# SCH_Output_register_2021-10-31.net
KiCad netlist of a schematic drawn in EasyEDA
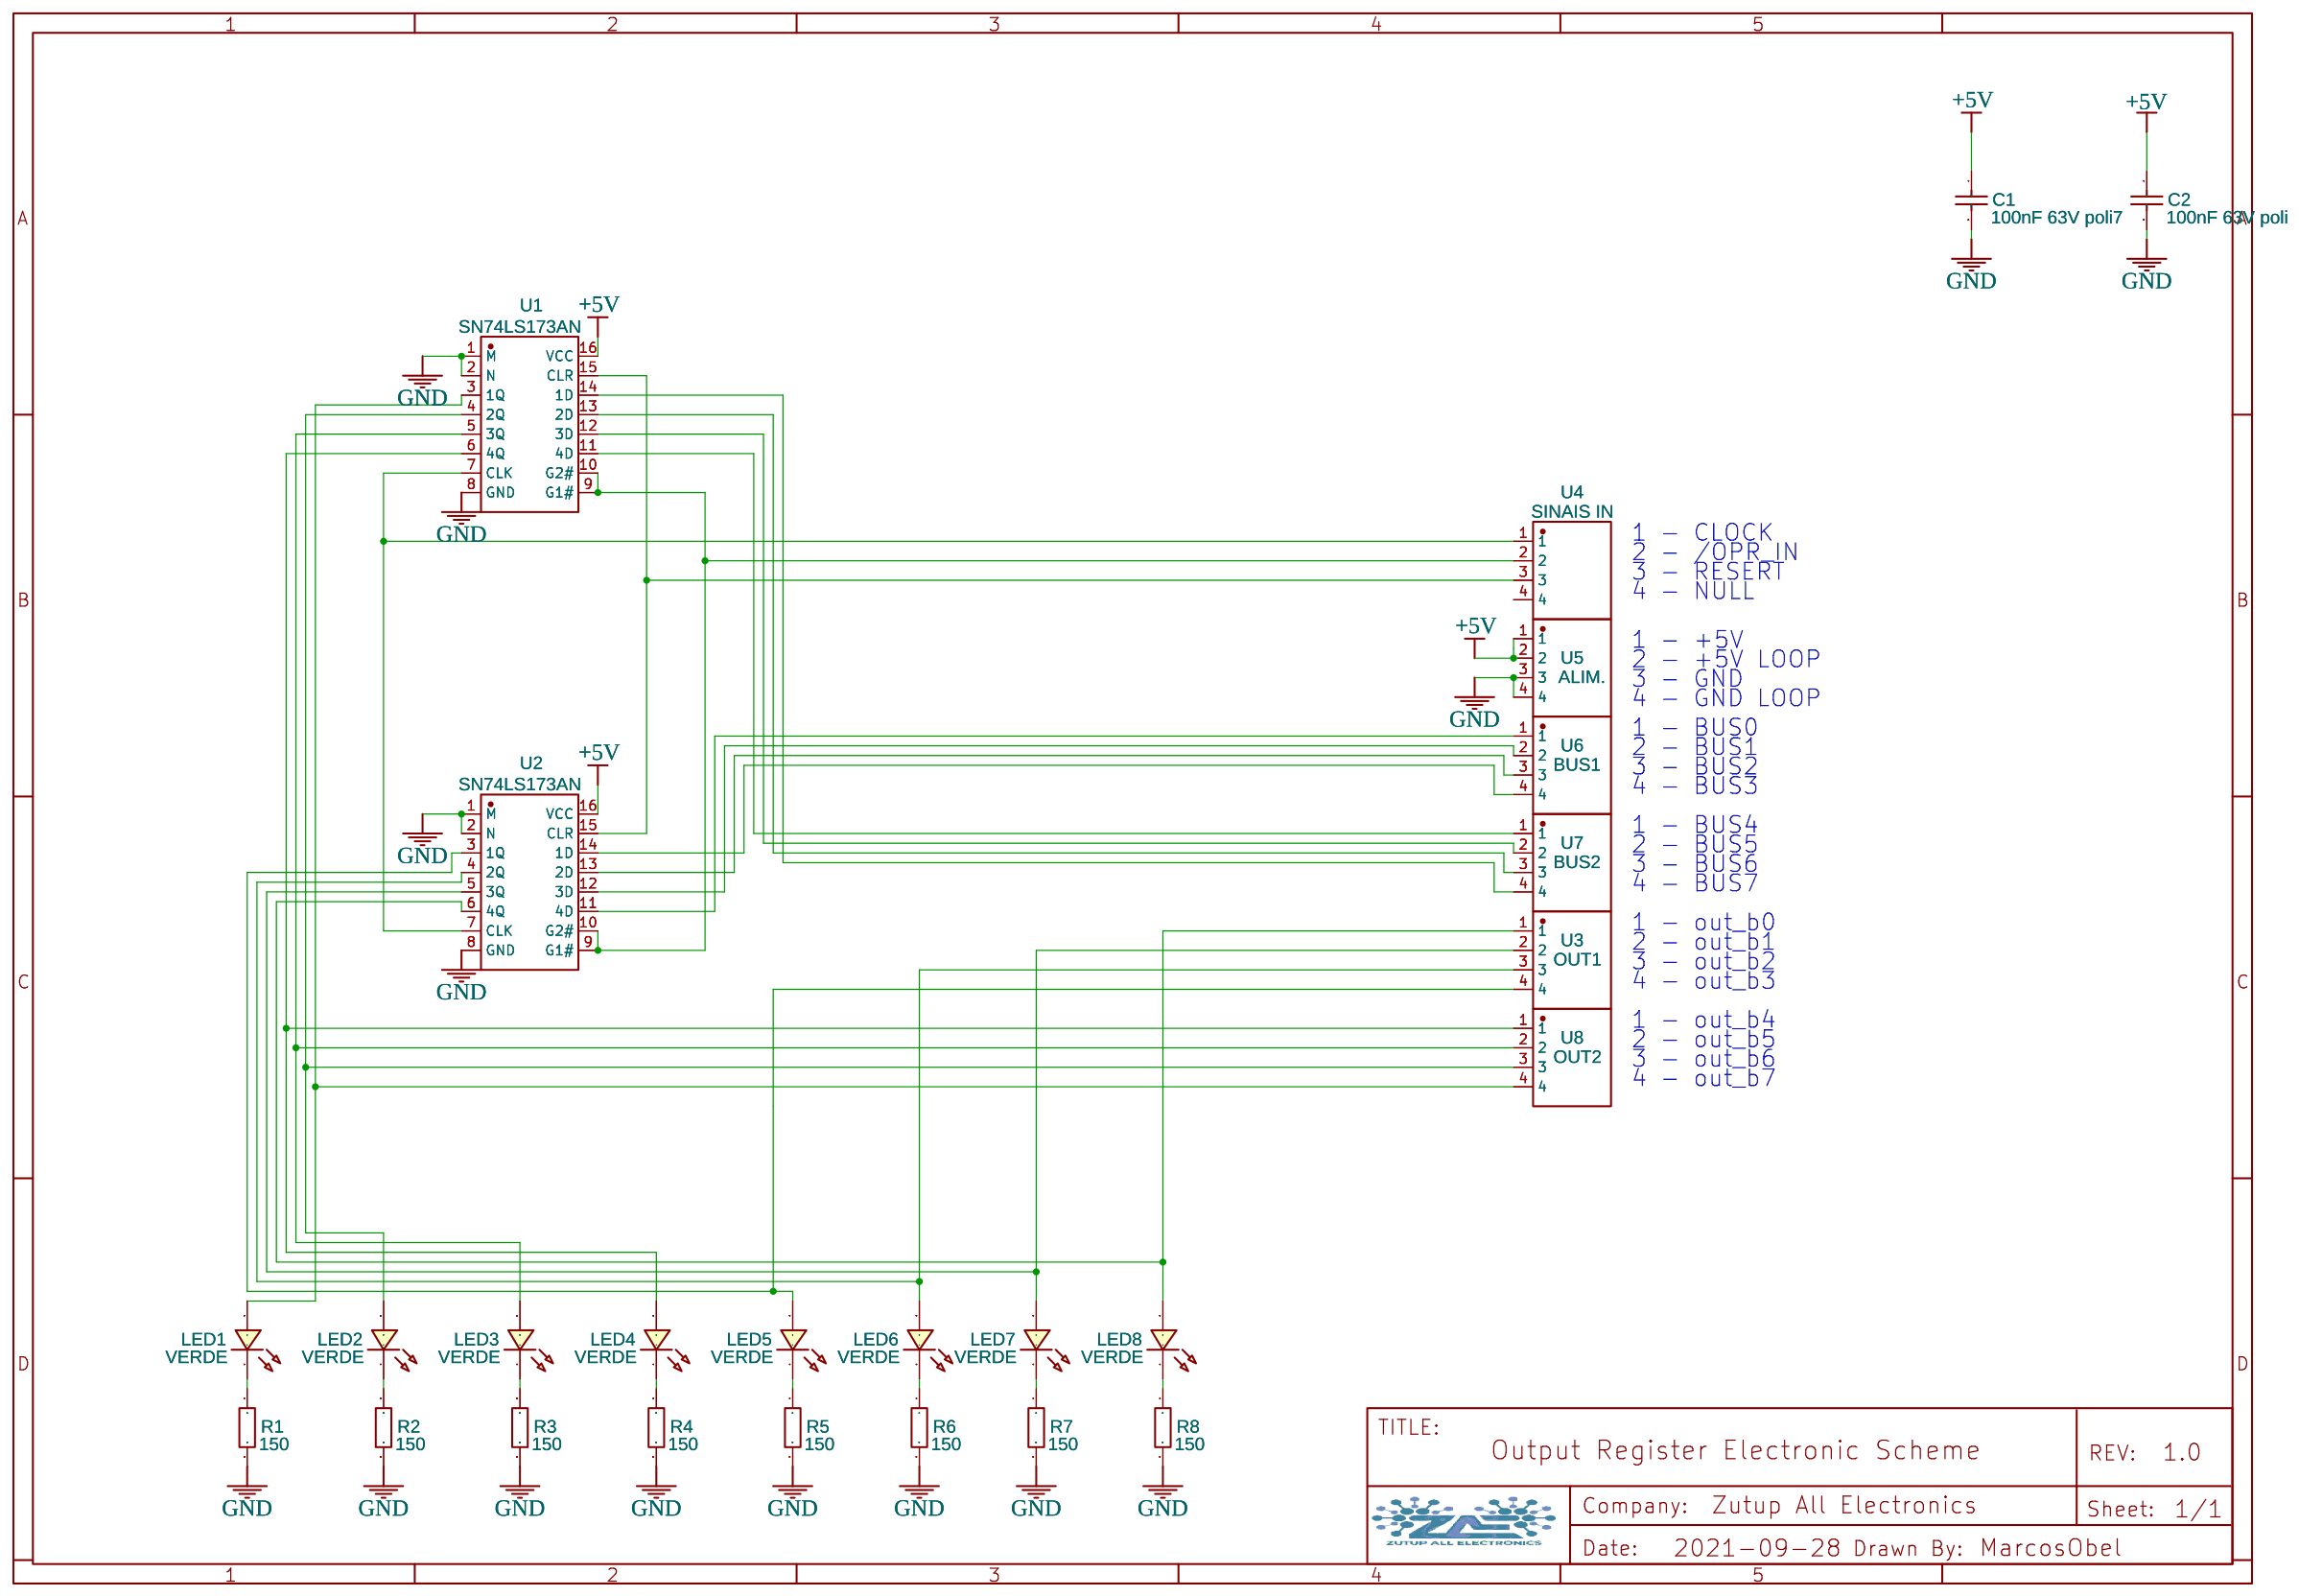
[diagram p0: schematic sheet]

(export (version "E")
  (design (tool "Eeschema 10.0.6"))
  (components
    (comp (ref "C1")
      (value "100nF 63V poli7")
      (fields
        (field (name "BOM_Manufacturer Part") "SR305C105KAR")
        (field (name "BOM_Supplier Part") "C444741")
      )
      (libsource (lib "") (part "SR305C105KAR"))
    )
    (comp (ref "C2")
      (value "100nF 63V poli")
      (fields
        (field (name "BOM_Manufacturer Part") "SR305C105KAR")
        (field (name "BOM_Supplier Part") "C444741")
      )
      (libsource (lib "") (part "SR305C105KAR"))
    )
    (comp (ref "LED1")
      (value "VERDE")
      (fields (field (name "BOM_Manufacturer Part") "264-7GD") (field (name "BOM_Supplier Part") "C605465"))
      (libsource (lib "") (part "264-7GD"))
    )
    (comp (ref "LED2")
      (value "VERDE")
      (fields (field (name "BOM_Manufacturer Part") "264-7GD") (field (name "BOM_Supplier Part") "C605465"))
      (libsource (lib "") (part "264-7GD"))
    )
    (comp (ref "LED3")
      (value "VERDE")
      (fields (field (name "BOM_Manufacturer Part") "264-7GD") (field (name "BOM_Supplier Part") "C605465"))
      (libsource (lib "") (part "264-7GD"))
    )
    (comp (ref "LED4")
      (value "VERDE")
      (fields (field (name "BOM_Manufacturer Part") "264-7GD") (field (name "BOM_Supplier Part") "C605465"))
      (libsource (lib "") (part "264-7GD"))
    )
    (comp (ref "LED5")
      (value "VERDE")
      (fields (field (name "BOM_Manufacturer Part") "264-7GD") (field (name "BOM_Supplier Part") "C605465"))
      (libsource (lib "") (part "264-7GD"))
    )
    (comp (ref "LED6")
      (value "VERDE")
      (fields (field (name "BOM_Manufacturer Part") "264-7GD") (field (name "BOM_Supplier Part") "C605465"))
      (libsource (lib "") (part "264-7GD"))
    )
    (comp (ref "LED7")
      (value "VERDE")
      (fields (field (name "BOM_Manufacturer Part") "264-7GD") (field (name "BOM_Supplier Part") "C605465"))
      (libsource (lib "") (part "264-7GD"))
    )
    (comp (ref "LED8")
      (value "VERDE")
      (fields (field (name "BOM_Manufacturer Part") "264-7GD") (field (name "BOM_Supplier Part") "C605465"))
      (libsource (lib "") (part "264-7GD"))
    )
    (comp (ref "R1")
      (value "150")
      (fields
        (field (name "BOM_Manufacturer Part") "CFR02SJ0823A10")
        (field (name "BOM_Supplier Part") "C69876")
      )
      (libsource (lib "") (part "CFR02SJ0823A10"))
    )
    (comp (ref "R2")
      (value "150")
      (fields
        (field (name "BOM_Manufacturer Part") "CFR02SJ0823A10")
        (field (name "BOM_Supplier Part") "C69876")
      )
      (libsource (lib "") (part "CFR02SJ0823A10"))
    )
    (comp (ref "R3")
      (value "150")
      (fields
        (field (name "BOM_Manufacturer Part") "CFR02SJ0823A10")
        (field (name "BOM_Supplier Part") "C69876")
      )
      (libsource (lib "") (part "CFR02SJ0823A10"))
    )
    (comp (ref "R4")
      (value "150")
      (fields
        (field (name "BOM_Manufacturer Part") "CFR02SJ0823A10")
        (field (name "BOM_Supplier Part") "C69876")
      )
      (libsource (lib "") (part "CFR02SJ0823A10"))
    )
    (comp (ref "R5")
      (value "150")
      (fields
        (field (name "BOM_Manufacturer Part") "CFR02SJ0823A10")
        (field (name "BOM_Supplier Part") "C69876")
      )
      (libsource (lib "") (part "CFR02SJ0823A10"))
    )
    (comp (ref "R6")
      (value "150")
      (fields
        (field (name "BOM_Manufacturer Part") "CFR02SJ0823A10")
        (field (name "BOM_Supplier Part") "C69876")
      )
      (libsource (lib "") (part "CFR02SJ0823A10"))
    )
    (comp (ref "R7")
      (value "150")
      (fields
        (field (name "BOM_Manufacturer Part") "CFR02SJ0823A10")
        (field (name "BOM_Supplier Part") "C69876")
      )
      (libsource (lib "") (part "CFR02SJ0823A10"))
    )
    (comp (ref "R8")
      (value "150")
      (fields
        (field (name "BOM_Manufacturer Part") "CFR02SJ0823A10")
        (field (name "BOM_Supplier Part") "C69876")
      )
      (libsource (lib "") (part "CFR02SJ0823A10"))
    )
    (comp (ref "U1")
      (value "SN74LS173AN")
      (fields (field (name "BOM_Supplier Part") "C1550125"))
      (libsource (lib "") (part "SN74LS173AN"))
    )
    (comp (ref "U2")
      (value "SN74LS173AN")
      (fields (field (name "BOM_Supplier Part") "C1550125"))
      (libsource (lib "") (part "SN74LS173AN"))
    )
    (comp (ref "U3")
      (value "OUT1")
      (fields (field (name "BOM_Manufacturer Part") "171825-4") (field (name "BOM_Supplier Part") "C210162"))
      (libsource (lib "") (part "171825-4"))
    )
    (comp (ref "U4")
      (value "SINAIS IN")
      (fields (field (name "BOM_Manufacturer Part") "171825-4") (field (name "BOM_Supplier Part") "C210162"))
      (libsource (lib "") (part "171825-4"))
    )
    (comp (ref "U5")
      (value "ALIM.")
      (fields (field (name "BOM_Manufacturer Part") "171825-4") (field (name "BOM_Supplier Part") "C210162"))
      (libsource (lib "") (part "171825-4"))
    )
    (comp (ref "U6")
      (value "BUS1")
      (fields (field (name "BOM_Manufacturer Part") "171825-4") (field (name "BOM_Supplier Part") "C210162"))
      (libsource (lib "") (part "171825-4"))
    )
    (comp (ref "U7")
      (value "BUS2")
      (fields (field (name "BOM_Manufacturer Part") "171825-4") (field (name "BOM_Supplier Part") "C210162"))
      (libsource (lib "") (part "171825-4"))
    )
    (comp (ref "U8")
      (value "OUT2")
      (fields (field (name "BOM_Manufacturer Part") "171825-4") (field (name "BOM_Supplier Part") "C210162"))
      (libsource (lib "") (part "171825-4"))
    )
  )
  (nets
    (net (code "1") (name "+5V") (class "Default")
      (node (ref "C1") (pin "1") (pinfunction "1_1") (pintype "input"))
      (node (ref "C2") (pin "1") (pinfunction "1_1") (pintype "input"))
      (node (ref "U1") (pin "16") (pinfunction "VCC_16") (pintype "unspecified"))
      (node (ref "U2") (pin "16") (pinfunction "VCC_16") (pintype "unspecified"))
      (node (ref "U5") (pin "1") (pinfunction "1_1") (pintype "unspecified"))
      (node (ref "U5") (pin "2") (pinfunction "2_2") (pintype "unspecified"))
    )
    (net (code "2") (name "GND") (class "Default")
      (node (ref "C1") (pin "2") (pinfunction "2_2") (pintype "input"))
      (node (ref "C2") (pin "2") (pinfunction "2_2") (pintype "input"))
      (node (ref "R1") (pin "2") (pinfunction "2_2") (pintype "input"))
      (node (ref "R2") (pin "2") (pinfunction "2_2") (pintype "input"))
      (node (ref "R3") (pin "2") (pinfunction "2_2") (pintype "input"))
      (node (ref "R4") (pin "2") (pinfunction "2_2") (pintype "input"))
      (node (ref "R5") (pin "2") (pinfunction "2_2") (pintype "input"))
      (node (ref "R6") (pin "2") (pinfunction "2_2") (pintype "input"))
      (node (ref "R7") (pin "2") (pinfunction "2_2") (pintype "input"))
      (node (ref "R8") (pin "2") (pinfunction "2_2") (pintype "input"))
      (node (ref "U1") (pin "1") (pinfunction "M_1") (pintype "unspecified"))
      (node (ref "U1") (pin "2") (pinfunction "N_2") (pintype "unspecified"))
      (node (ref "U1") (pin "8") (pinfunction "GND_8") (pintype "unspecified"))
      (node (ref "U2") (pin "1") (pinfunction "M_1") (pintype "unspecified"))
      (node (ref "U2") (pin "2") (pinfunction "N_2") (pintype "unspecified"))
      (node (ref "U2") (pin "8") (pinfunction "GND_8") (pintype "unspecified"))
      (node (ref "U5") (pin "3") (pinfunction "3_3") (pintype "unspecified"))
      (node (ref "U5") (pin "4") (pinfunction "4_4") (pintype "unspecified"))
    )
    (net (code "3") (name "Net-(LED1-+)") (class "Default")
      (node (ref "LED1") (pin "2") (pinfunction "+_2") (pintype "unspecified"))
      (node (ref "U1") (pin "3") (pinfunction "1Q_3") (pintype "unspecified"))
      (node (ref "U8") (pin "4") (pinfunction "4_4") (pintype "unspecified"))
    )
    (net (code "4") (name "Net-(LED1--)") (class "Default")
      (node (ref "LED1") (pin "1") (pinfunction "-_1") (pintype "unspecified"))
      (node (ref "R1") (pin "1") (pinfunction "1_1") (pintype "input"))
    )
    (net (code "5") (name "Net-(LED2-+)") (class "Default")
      (node (ref "LED2") (pin "2") (pinfunction "+_2") (pintype "unspecified"))
      (node (ref "U1") (pin "4") (pinfunction "2Q_4") (pintype "unspecified"))
      (node (ref "U8") (pin "3") (pinfunction "3_3") (pintype "unspecified"))
    )
    (net (code "6") (name "Net-(LED2--)") (class "Default")
      (node (ref "LED2") (pin "1") (pinfunction "-_1") (pintype "unspecified"))
      (node (ref "R2") (pin "1") (pinfunction "1_1") (pintype "input"))
    )
    (net (code "7") (name "Net-(LED3-+)") (class "Default")
      (node (ref "LED3") (pin "2") (pinfunction "+_2") (pintype "unspecified"))
      (node (ref "U1") (pin "5") (pinfunction "3Q_5") (pintype "unspecified"))
      (node (ref "U8") (pin "2") (pinfunction "2_2") (pintype "unspecified"))
    )
    (net (code "8") (name "Net-(LED3--)") (class "Default")
      (node (ref "LED3") (pin "1") (pinfunction "-_1") (pintype "unspecified"))
      (node (ref "R3") (pin "1") (pinfunction "1_1") (pintype "input"))
    )
    (net (code "9") (name "Net-(LED4-+)") (class "Default")
      (node (ref "LED4") (pin "2") (pinfunction "+_2") (pintype "unspecified"))
      (node (ref "U1") (pin "6") (pinfunction "4Q_6") (pintype "unspecified"))
      (node (ref "U8") (pin "1") (pinfunction "1_1") (pintype "unspecified"))
    )
    (net (code "10") (name "Net-(LED4--)") (class "Default")
      (node (ref "LED4") (pin "1") (pinfunction "-_1") (pintype "unspecified"))
      (node (ref "R4") (pin "1") (pinfunction "1_1") (pintype "input"))
    )
    (net (code "11") (name "Net-(LED5-+)") (class "Default")
      (node (ref "LED5") (pin "2") (pinfunction "+_2") (pintype "unspecified"))
      (node (ref "U2") (pin "3") (pinfunction "1Q_3") (pintype "unspecified"))
      (node (ref "U3") (pin "4") (pinfunction "4_4") (pintype "unspecified"))
    )
    (net (code "12") (name "Net-(LED5--)") (class "Default")
      (node (ref "LED5") (pin "1") (pinfunction "-_1") (pintype "unspecified"))
      (node (ref "R5") (pin "1") (pinfunction "1_1") (pintype "input"))
    )
    (net (code "13") (name "Net-(LED6-+)") (class "Default")
      (node (ref "LED6") (pin "2") (pinfunction "+_2") (pintype "unspecified"))
      (node (ref "U2") (pin "4") (pinfunction "2Q_4") (pintype "unspecified"))
      (node (ref "U3") (pin "3") (pinfunction "3_3") (pintype "unspecified"))
    )
    (net (code "14") (name "Net-(LED6--)") (class "Default")
      (node (ref "LED6") (pin "1") (pinfunction "-_1") (pintype "unspecified"))
      (node (ref "R6") (pin "1") (pinfunction "1_1") (pintype "input"))
    )
    (net (code "15") (name "Net-(LED7-+)") (class "Default")
      (node (ref "LED7") (pin "2") (pinfunction "+_2") (pintype "unspecified"))
      (node (ref "U2") (pin "5") (pinfunction "3Q_5") (pintype "unspecified"))
      (node (ref "U3") (pin "2") (pinfunction "2_2") (pintype "unspecified"))
    )
    (net (code "16") (name "Net-(LED7--)") (class "Default")
      (node (ref "LED7") (pin "1") (pinfunction "-_1") (pintype "unspecified"))
      (node (ref "R7") (pin "1") (pinfunction "1_1") (pintype "input"))
    )
    (net (code "17") (name "Net-(LED8-+)") (class "Default")
      (node (ref "LED8") (pin "2") (pinfunction "+_2") (pintype "unspecified"))
      (node (ref "U2") (pin "6") (pinfunction "4Q_6") (pintype "unspecified"))
      (node (ref "U3") (pin "1") (pinfunction "1_1") (pintype "unspecified"))
    )
    (net (code "18") (name "Net-(LED8--)") (class "Default")
      (node (ref "LED8") (pin "1") (pinfunction "-_1") (pintype "unspecified"))
      (node (ref "R8") (pin "1") (pinfunction "1_1") (pintype "input"))
    )
    (net (code "19") (name "Net-(U1-1D)") (class "Default")
      (node (ref "U1") (pin "14") (pinfunction "1D_14") (pintype "unspecified"))
      (node (ref "U7") (pin "4") (pinfunction "4_4") (pintype "unspecified"))
    )
    (net (code "20") (name "Net-(U1-2D)") (class "Default")
      (node (ref "U1") (pin "13") (pinfunction "2D_13") (pintype "unspecified"))
      (node (ref "U7") (pin "3") (pinfunction "3_3") (pintype "unspecified"))
    )
    (net (code "21") (name "Net-(U1-3D)") (class "Default")
      (node (ref "U1") (pin "12") (pinfunction "3D_12") (pintype "unspecified"))
      (node (ref "U7") (pin "2") (pinfunction "2_2") (pintype "unspecified"))
    )
    (net (code "22") (name "Net-(U1-4D)") (class "Default")
      (node (ref "U1") (pin "11") (pinfunction "4D_11") (pintype "unspecified"))
      (node (ref "U7") (pin "1") (pinfunction "1_1") (pintype "unspecified"))
    )
    (net (code "23") (name "Net-(U1-CLK)") (class "Default")
      (node (ref "U1") (pin "7") (pinfunction "CLK_7") (pintype "unspecified"))
      (node (ref "U2") (pin "7") (pinfunction "CLK_7") (pintype "unspecified"))
      (node (ref "U4") (pin "1") (pinfunction "1_1") (pintype "unspecified"))
    )
    (net (code "24") (name "Net-(U1-CLR)") (class "Default")
      (node (ref "U1") (pin "15") (pinfunction "CLR_15") (pintype "unspecified"))
      (node (ref "U2") (pin "15") (pinfunction "CLR_15") (pintype "unspecified"))
      (node (ref "U4") (pin "3") (pinfunction "3_3") (pintype "unspecified"))
    )
    (net (code "25") (name "Net-(U1-G1#)") (class "Default")
      (node (ref "U1") (pin "10") (pinfunction "G2#_10") (pintype "unspecified"))
      (node (ref "U1") (pin "9") (pinfunction "G1#_9") (pintype "unspecified"))
      (node (ref "U2") (pin "10") (pinfunction "G2#_10") (pintype "unspecified"))
      (node (ref "U2") (pin "9") (pinfunction "G1#_9") (pintype "unspecified"))
      (node (ref "U4") (pin "2") (pinfunction "2_2") (pintype "unspecified"))
    )
    (net (code "26") (name "Net-(U2-1D)") (class "Default")
      (node (ref "U2") (pin "14") (pinfunction "1D_14") (pintype "unspecified"))
      (node (ref "U6") (pin "4") (pinfunction "4_4") (pintype "unspecified"))
    )
    (net (code "27") (name "Net-(U2-2D)") (class "Default")
      (node (ref "U2") (pin "13") (pinfunction "2D_13") (pintype "unspecified"))
      (node (ref "U6") (pin "3") (pinfunction "3_3") (pintype "unspecified"))
    )
    (net (code "28") (name "Net-(U2-3D)") (class "Default")
      (node (ref "U2") (pin "12") (pinfunction "3D_12") (pintype "unspecified"))
      (node (ref "U6") (pin "2") (pinfunction "2_2") (pintype "unspecified"))
    )
    (net (code "29") (name "Net-(U2-4D)") (class "Default")
      (node (ref "U2") (pin "11") (pinfunction "4D_11") (pintype "unspecified"))
      (node (ref "U6") (pin "1") (pinfunction "1_1") (pintype "unspecified"))
    )
    (net (code "30") (name "unconnected-(U4-Pad4)") (class "Default")
      (node (ref "U4") (pin "4") (pinfunction "4_4") (pintype "unspecified"))
    )
  )
)
